# FinishLine.net
KiCad netlist of a schematic drawn in EAGLE
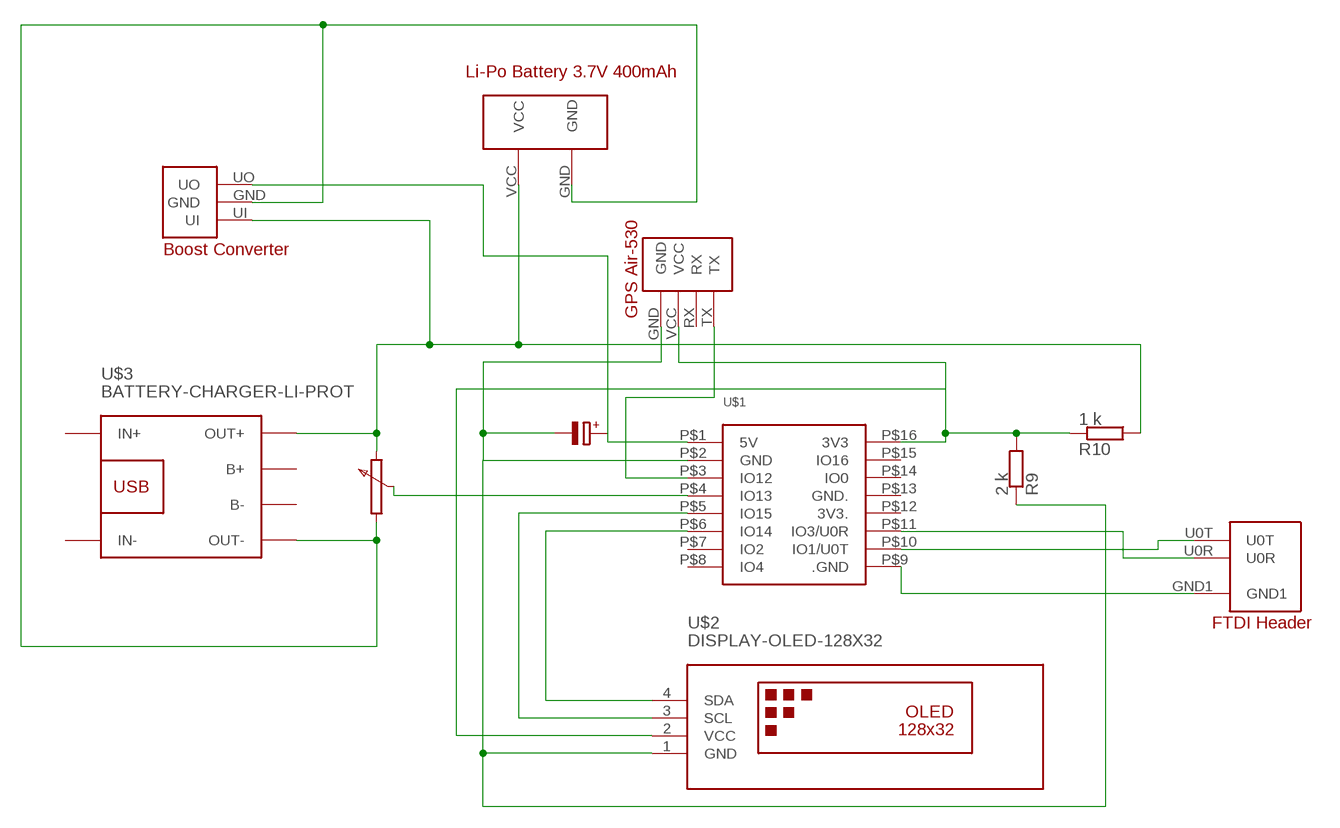
[diagram p0: schematic, sheet 1]

(export (version "E")
  (design (tool "Eeschema 10.0.6"))
  (components
    (comp (ref "R9")
      (value "2 k")
      (footprint "eagle-import:SMT-REF")
      (libsource (lib "eagle-import") (part "SMT-REF"))
    )
    (comp (ref "R10")
      (value "1 k")
      (footprint "eagle-import:SMT-REF")
      (libsource (lib "eagle-import") (part "SMT-REF"))
    )
    (comp (ref "U$1")
      (value "ESP32-CAM")
      (footprint "eagle-import:ESP32-CAM")
      (fields (field (name "MF") "AI-Thinker"))
      (libsource (lib "eagle-import") (part "ESP32-CAM"))
    )
    (comp (ref "U$2")
      (value "DISPLAY-OLED-128X32")
      (footprint "eagle-import:DISPLAY-OLED-128X32")
      (libsource (lib "eagle-import") (part "DISPLAY-OLED-128X32"))
    )
    (comp (ref "U$3")
      (value "BATTERY-CHARGER-LI-PROT")
      (footprint "eagle-import:BATTERY-CHARGER-LI-PROT")
      (libsource (lib "eagle-import") (part "BATTERY-CHARGER-LI-PROT"))
    )
    (comp (ref "U$4")
      (value "GPS")
      (footprint "eagle-import:GPS")
      (libsource (lib "eagle-import") (part "GPS"))
    )
    (comp (ref "U$5")
      (value "BOOST_CONVERTER")
      (footprint "eagle-import:BOOST_CONVERTER")
      (libsource (lib "eagle-import") (part "BOOST_CONVERTER"))
    )
    (comp (ref "U$6")
      (value "LIPO_BAT")
      (footprint "eagle-import:LIPO_BAT")
      (libsource (lib "eagle-import") (part "LIPO_BAT"))
    )
    (comp (ref "U$7")
      (value "HEADER_FTDI")
      (footprint "eagle-import:HEADER_FTDI")
      (libsource (lib "eagle-import") (part "HEADER_FTDI"))
    )
  )
  (nets
    (net (code "1") (name "Net-(R10-Pad1)") (class "Default")
      (node (ref "R10") (pin "1") (pinfunction "1_1") (pintype "passive"))
      (node (ref "U$3") (pin "OUT+") (pinfunction "OUT+_OUT+") (pintype "bidirectional"))
      (node (ref "U$5") (pin "UI") (pinfunction "UI_UI") (pintype "bidirectional"))
      (node (ref "U$6") (pin "VCC") (pinfunction "VCC_VCC") (pintype "bidirectional"))
    )
    (net (code "2") (name "Net-(U$1-.GND)") (class "Default")
      (node (ref "U$1") (pin "P$9") (pinfunction ".GND_P$9") (pintype "bidirectional"))
      (node (ref "U$7") (pin "GND1") (pinfunction "GND1_GND1") (pintype "bidirectional"))
    )
    (net (code "3") (name "Net-(U$1-3V3)") (class "Default")
      (node (ref "R10") (pin "2") (pinfunction "2_2") (pintype "passive"))
      (node (ref "R9") (pin "1") (pinfunction "1_1") (pintype "passive"))
      (node (ref "U$1") (pin "P$16") (pinfunction "3V3_P$16") (pintype "bidirectional"))
      (node (ref "U$2") (pin "2") (pinfunction "VCC_2") (pintype "power_in"))
      (node (ref "U$4") (pin "VCC") (pinfunction "VCC_VCC") (pintype "bidirectional"))
    )
    (net (code "4") (name "Net-(U$1-5V)") (class "Default")
      (node (ref "U$1") (pin "P$1") (pinfunction "5V_P$1") (pintype "bidirectional"))
      (node (ref "U$5") (pin "UO") (pinfunction "UO_UO") (pintype "bidirectional"))
    )
    (net (code "5") (name "Net-(U$1-GND)") (class "Default")
      (node (ref "R9") (pin "2") (pinfunction "2_2") (pintype "passive"))
      (node (ref "U$1") (pin "P$2") (pinfunction "GND_P$2") (pintype "bidirectional"))
      (node (ref "U$2") (pin "1") (pinfunction "GND_1") (pintype "power_in"))
      (node (ref "U$4") (pin "GND") (pinfunction "GND_GND") (pintype "bidirectional"))
    )
    (net (code "6") (name "Net-(U$1-IO1{slash}U0T)") (class "Default")
      (node (ref "U$1") (pin "P$10") (pinfunction "IO1/U0T_P$10") (pintype "bidirectional"))
      (node (ref "U$7") (pin "U0T") (pinfunction "U0T_U0T") (pintype "bidirectional"))
    )
    (net (code "7") (name "Net-(U$1-IO3{slash}U0R)") (class "Default")
      (node (ref "U$1") (pin "P$11") (pinfunction "IO3/U0R_P$11") (pintype "bidirectional"))
      (node (ref "U$7") (pin "U0R") (pinfunction "U0R_U0R") (pintype "bidirectional"))
    )
    (net (code "8") (name "Net-(U$1-IO12)") (class "Default")
      (node (ref "U$1") (pin "P$3") (pinfunction "IO12_P$3") (pintype "bidirectional"))
      (node (ref "U$4") (pin "TX") (pinfunction "TX_TX") (pintype "bidirectional"))
    )
    (net (code "9") (name "Net-(U$1-IO14)") (class "Default")
      (node (ref "U$1") (pin "P$6") (pinfunction "IO14_P$6") (pintype "bidirectional"))
      (node (ref "U$2") (pin "4") (pinfunction "SDA_4") (pintype "bidirectional"))
    )
    (net (code "10") (name "Net-(U$1-IO15)") (class "Default")
      (node (ref "U$1") (pin "P$5") (pinfunction "IO15_P$5") (pintype "bidirectional"))
      (node (ref "U$2") (pin "3") (pinfunction "SCL_3") (pintype "bidirectional"))
    )
    (net (code "11") (name "Net-(U$3-PadOUT-)") (class "Default")
      (node (ref "U$3") (pin "OUT-") (pinfunction "OUT-_OUT-") (pintype "bidirectional"))
      (node (ref "U$5") (pin "GND") (pinfunction "GND_GND") (pintype "bidirectional"))
      (node (ref "U$6") (pin "GND") (pinfunction "GND_GND") (pintype "bidirectional"))
    )
    (net (code "12") (name "unconnected-(U$1-3V3.-PadP$12)") (class "Default")
      (node (ref "U$1") (pin "P$12") (pinfunction "3V3._P$12") (pintype "bidirectional"))
    )
    (net (code "13") (name "unconnected-(U$1-GND.-PadP$13)") (class "Default")
      (node (ref "U$1") (pin "P$13") (pinfunction "GND._P$13") (pintype "bidirectional"))
    )
    (net (code "14") (name "unconnected-(U$1-IO0-PadP$14)") (class "Default")
      (node (ref "U$1") (pin "P$14") (pinfunction "IO0_P$14") (pintype "bidirectional"))
    )
    (net (code "15") (name "unconnected-(U$1-IO2-PadP$7)") (class "Default")
      (node (ref "U$1") (pin "P$7") (pinfunction "IO2_P$7") (pintype "bidirectional"))
    )
    (net (code "16") (name "unconnected-(U$1-IO4-PadP$8)") (class "Default")
      (node (ref "U$1") (pin "P$8") (pinfunction "IO4_P$8") (pintype "bidirectional"))
    )
    (net (code "17") (name "unconnected-(U$1-IO13-PadP$4)") (class "Default")
      (node (ref "U$1") (pin "P$4") (pinfunction "IO13_P$4") (pintype "bidirectional"))
    )
    (net (code "18") (name "unconnected-(U$1-IO16-PadP$15)") (class "Default")
      (node (ref "U$1") (pin "P$15") (pinfunction "IO16_P$15") (pintype "bidirectional"))
    )
    (net (code "19") (name "unconnected-(U$3-PadB+)") (class "Default")
      (node (ref "U$3") (pin "B+") (pinfunction "B+_B+") (pintype "bidirectional"))
    )
    (net (code "20") (name "unconnected-(U$3-PadB-)") (class "Default")
      (node (ref "U$3") (pin "B-") (pinfunction "B-_B-") (pintype "bidirectional"))
    )
    (net (code "21") (name "unconnected-(U$3-PadIN+)") (class "Default")
      (node (ref "U$3") (pin "IN+") (pinfunction "IN+_IN+") (pintype "bidirectional"))
    )
    (net (code "22") (name "unconnected-(U$3-PadIN-)") (class "Default")
      (node (ref "U$3") (pin "IN-") (pinfunction "IN-_IN-") (pintype "bidirectional"))
    )
    (net (code "23") (name "unconnected-(U$4-PadRX)") (class "Default")
      (node (ref "U$4") (pin "RX") (pinfunction "RX_RX") (pintype "bidirectional"))
    )
  )
)
